# tritiled22_xpe.net
KiCad netlist of a schematic drawn in EAGLE
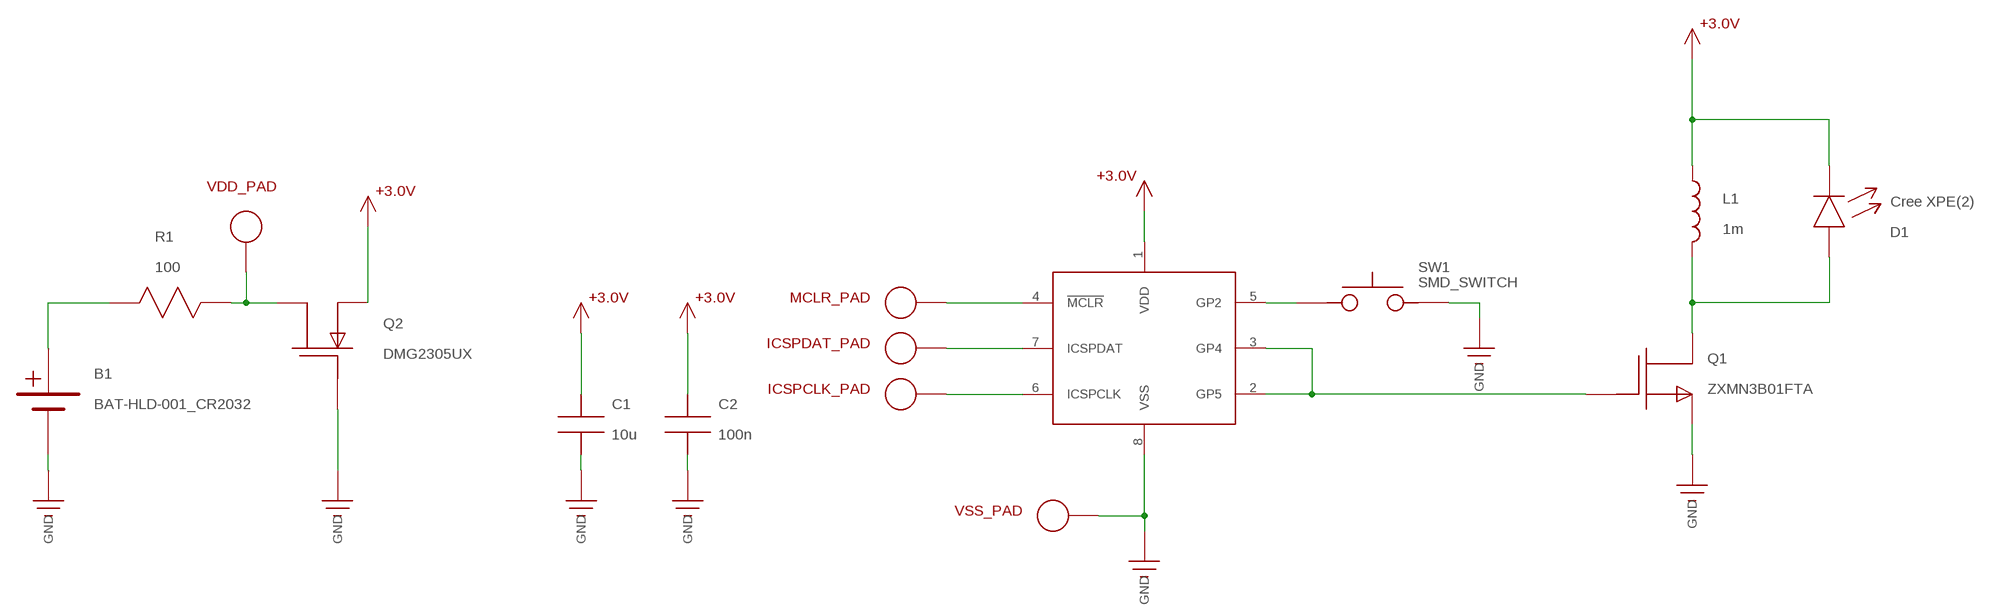
[diagram p0: schematic, sheet 1]

(export (version "E")
  (design (tool "Eeschema 10.0.6"))
  (components
    (comp (ref "B1")
      (value "BAT-HLD-001_CR2032")
      (footprint "eagle-import:CR2032_BAT-HLD_001")
      (libsource (lib "eagle-import") (part "BAT-HLD-001_CR2032"))
    )
    (comp (ref "C1")
      (value "10u")
      (footprint "eagle-import:1206")
      (libsource (lib "eagle-import") (part "C1206"))
    )
    (comp (ref "C2")
      (value "100n")
      (footprint "eagle-import:0805")
      (libsource (lib "eagle-import") (part "C0805"))
    )
    (comp (ref "D1")
      (value "Cree XPE(2)")
      (footprint "eagle-import:CREE_XPE_LED")
      (libsource (lib "eagle-import") (part "LEDCREE_XPE"))
    )
    (comp (ref "ICSPCLK_PAD")
      (value "ICSP_PAD")
      (footprint "eagle-import:ICSP_PAD")
      (libsource (lib "eagle-import") (part "ICSP_PAD"))
    )
    (comp (ref "ICSPDAT_PAD")
      (value "ICSP_PAD")
      (footprint "eagle-import:ICSP_PAD")
      (libsource (lib "eagle-import") (part "ICSP_PAD"))
    )
    (comp (ref "L1")
      (value "1m")
      (footprint "eagle-import:SRR6028_INDUCTOR")
      (libsource (lib "eagle-import") (part "SRR6028_INDUCTOR"))
    )
    (comp (ref "MCLR_PAD")
      (value "ICSP_PAD")
      (footprint "eagle-import:ICSP_PAD")
      (libsource (lib "eagle-import") (part "ICSP_PAD"))
    )
    (comp (ref "Q1")
      (value "ZXMN3B01FTA")
      (footprint "eagle-import:SOT-23")
      (libsource (lib "eagle-import") (part "ZXMN3B01FSOT23"))
    )
    (comp (ref "Q2")
      (value "DMG2305UX")
      (footprint "eagle-import:SOT-23")
      (libsource (lib "eagle-import") (part "DMG2305UXSOT23"))
    )
    (comp (ref "R1")
      (value "100")
      (footprint "eagle-import:R1206")
      (libsource (lib "eagle-import") (part "R1206"))
    )
    (comp (ref "SW1")
      (value "SMD_SWITCH")
      (footprint "eagle-import:SMD_SWITCH")
      (libsource (lib "eagle-import") (part "SMD_SWITCH"))
    )
    (comp (ref "U1")
      (value "PIC12LF1571")
      (footprint "eagle-import:SOIC8")
      (libsource (lib "eagle-import") (part "PIC12LF1571"))
    )
    (comp (ref "VDD_PAD")
      (value "ICSP_PAD")
      (footprint "eagle-import:ICSP_PAD")
      (libsource (lib "eagle-import") (part "ICSP_PAD"))
    )
    (comp (ref "VSS_PAD")
      (value "ICSP_PAD")
      (footprint "eagle-import:ICSP_PAD")
      (libsource (lib "eagle-import") (part "ICSP_PAD"))
    )
  )
  (nets
    (net (code "1") (name "+3.0V") (class "Default")
      (node (ref "C1") (pin "P$1") (pinfunction "P$1_P$1") (pintype "bidirectional"))
      (node (ref "C2") (pin "P$1") (pinfunction "P$1_P$1") (pintype "bidirectional"))
      (node (ref "D1") (pin "C") (pinfunction "C_C") (pintype "bidirectional"))
      (node (ref "L1") (pin "P$1") (pinfunction "1_P$1") (pintype "passive"))
      (node (ref "Q2") (pin "2") (pinfunction "S_2") (pintype "bidirectional"))
      (node (ref "U1") (pin "1") (pinfunction "VDD_1") (pintype "bidirectional"))
    )
    (net (code "2") (name "GND") (class "Default")
      (node (ref "B1") (pin "GND") (pinfunction "0V_GND") (pintype "power_in"))
      (node (ref "C1") (pin "P$2") (pinfunction "P$2_P$2") (pintype "bidirectional"))
      (node (ref "C2") (pin "P$2") (pinfunction "P$2_P$2") (pintype "bidirectional"))
      (node (ref "Q1") (pin "2") (pinfunction "S_2") (pintype "bidirectional"))
      (node (ref "Q2") (pin "1") (pinfunction "G_1") (pintype "bidirectional"))
      (node (ref "SW1") (pin "P$3") (pinfunction "P$2_P$3") (pintype "bidirectional"))
      (node (ref "SW1") (pin "P$4") (pinfunction "P$2_P$4") (pintype "bidirectional"))
      (node (ref "U1") (pin "8") (pinfunction "VSS_8") (pintype "bidirectional"))
      (node (ref "VSS_PAD") (pin "P$2") (pinfunction "P$1_P$2") (pintype "bidirectional"))
    )
    (net (code "3") (name "Net-(B1-+V-Pad+V1)") (class "Default")
      (node (ref "B1") (pin "+V1") (pinfunction "+V_+V1") (pintype "power_in"))
      (node (ref "B1") (pin "+V2") (pinfunction "+V_+V2") (pintype "power_in"))
      (node (ref "R1") (pin "P$1") (pinfunction "P$1_P$1") (pintype "bidirectional"))
    )
    (net (code "4") (name "Net-(ICSPCLK_PAD-P$1)") (class "Default")
      (node (ref "ICSPCLK_PAD") (pin "P$2") (pinfunction "P$1_P$2") (pintype "bidirectional"))
      (node (ref "U1") (pin "6") (pinfunction "ICSPCLK_6") (pintype "bidirectional"))
    )
    (net (code "5") (name "Net-(ICSPDAT_PAD-P$1)") (class "Default")
      (node (ref "ICSPDAT_PAD") (pin "P$2") (pinfunction "P$1_P$2") (pintype "bidirectional"))
      (node (ref "U1") (pin "7") (pinfunction "ICSPDAT_7") (pintype "bidirectional"))
    )
    (net (code "6") (name "Net-(L1-2)") (class "Default")
      (node (ref "D1") (pin "A") (pinfunction "A_A") (pintype "bidirectional"))
      (node (ref "L1") (pin "P$2") (pinfunction "2_P$2") (pintype "passive"))
      (node (ref "Q1") (pin "3") (pinfunction "D_3") (pintype "bidirectional"))
    )
    (net (code "7") (name "Net-(MCLR_PAD-P$1)") (class "Default")
      (node (ref "MCLR_PAD") (pin "P$2") (pinfunction "P$1_P$2") (pintype "bidirectional"))
      (node (ref "U1") (pin "4") (pinfunction "~{MCLR}_4") (pintype "bidirectional"))
    )
    (net (code "8") (name "Net-(Q1-G)") (class "Default")
      (node (ref "Q1") (pin "1") (pinfunction "G_1") (pintype "bidirectional"))
      (node (ref "U1") (pin "2") (pinfunction "GP5_2") (pintype "bidirectional"))
      (node (ref "U1") (pin "3") (pinfunction "GP4_3") (pintype "bidirectional"))
    )
    (net (code "9") (name "Net-(Q2-D)") (class "Default")
      (node (ref "Q2") (pin "3") (pinfunction "D_3") (pintype "bidirectional"))
      (node (ref "R1") (pin "P$2") (pinfunction "P$2_P$2") (pintype "bidirectional"))
      (node (ref "VDD_PAD") (pin "P$2") (pinfunction "P$1_P$2") (pintype "bidirectional"))
    )
    (net (code "10") (name "Net-(U1-GP2)") (class "Default")
      (node (ref "SW1") (pin "P$1") (pinfunction "P$1_P$1") (pintype "bidirectional"))
      (node (ref "SW1") (pin "P$2") (pinfunction "P$1_P$2") (pintype "bidirectional"))
      (node (ref "U1") (pin "5") (pinfunction "GP2_5") (pintype "bidirectional"))
    )
  )
)
